# 16Bit_Group_Ripple_Adder.net
KiCad netlist of a schematic drawn in Altium Designer
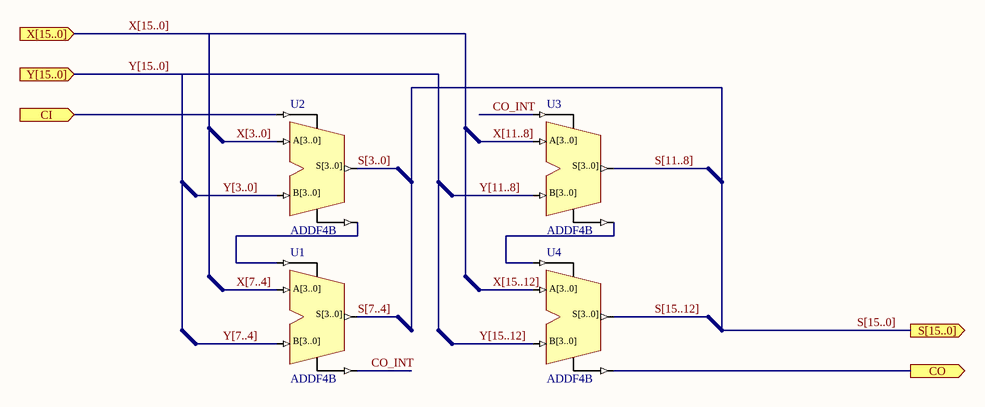
[diagram p0: 16Bit Group Ripple Adder.SchDoc]

(export (version "E")
  (design (tool "Eeschema 10.0.6"))
  (components
    (comp (ref "U1")
      (value "ADDF4B")
      (description "4-Bit Cascadable Unsigned Binary Full Adder, Bus Version")
      (fields (field (name "PUBLISHER") "Altium Limited"))
      (libsource (lib "FPGA Generic") (part "ADDF4B"))
    )
    (comp (ref "U2")
      (value "ADDF4B")
      (description "4-Bit Cascadable Unsigned Binary Full Adder, Bus Version")
      (fields (field (name "PUBLISHER") "Altium Limited"))
      (libsource (lib "FPGA Generic") (part "ADDF4B"))
    )
    (comp (ref "U3")
      (value "ADDF4B")
      (description "4-Bit Cascadable Unsigned Binary Full Adder, Bus Version")
      (fields (field (name "PUBLISHER") "Altium Limited"))
      (libsource (lib "FPGA Generic") (part "ADDF4B"))
    )
    (comp (ref "U4")
      (value "ADDF4B")
      (description "4-Bit Cascadable Unsigned Binary Full Adder, Bus Version")
      (fields (field (name "PUBLISHER") "Altium Limited"))
      (libsource (lib "FPGA Generic") (part "ADDF4B"))
    )
  )
  (nets
    (net (code "49") (name "/CI") (class "Default")
      (node (ref "U2") (pin "CI") (pinfunction "CI_CI") (pintype "input"))
    )
    (net (code "50") (name "/CO") (class "Default")
      (node (ref "U4") (pin "CO") (pinfunction "CO_CO") (pintype "output"))
    )
    (net (code "51") (name "/CO_INT") (class "Default")
      (node (ref "U1") (pin "CO") (pinfunction "CO_CO") (pintype "output"))
      (node (ref "U3") (pin "CI") (pinfunction "CI_CI") (pintype "input"))
    )
    (net (code "52") (name "/S[3..0]") (class "Default")
      (node (ref "U2") (pin "S[3..0]") (pinfunction "S[3..0]_S[3..0]") (pintype "output"))
    )
    (net (code "53") (name "/S[7..4]") (class "Default")
      (node (ref "U1") (pin "S[3..0]") (pinfunction "S[3..0]_S[3..0]") (pintype "output"))
    )
    (net (code "54") (name "/S[11..8]") (class "Default")
      (node (ref "U3") (pin "S[3..0]") (pinfunction "S[3..0]_S[3..0]") (pintype "output"))
    )
    (net (code "56") (name "/S[15..12]") (class "Default")
      (node (ref "U4") (pin "S[3..0]") (pinfunction "S[3..0]_S[3..0]") (pintype "output"))
    )
    (net (code "57") (name "/X[3..0]") (class "Default")
      (node (ref "U2") (pin "A[3..0]") (pinfunction "A[3..0]_A[3..0]") (pintype "input"))
    )
    (net (code "58") (name "/X[7..4]") (class "Default")
      (node (ref "U1") (pin "A[3..0]") (pinfunction "A[3..0]_A[3..0]") (pintype "input"))
    )
    (net (code "59") (name "/X[11..8]") (class "Default")
      (node (ref "U3") (pin "A[3..0]") (pinfunction "A[3..0]_A[3..0]") (pintype "input"))
    )
    (net (code "61") (name "/X[15..12]") (class "Default")
      (node (ref "U4") (pin "A[3..0]") (pinfunction "A[3..0]_A[3..0]") (pintype "input"))
    )
    (net (code "62") (name "/Y[3..0]") (class "Default")
      (node (ref "U2") (pin "B[3..0]") (pinfunction "B[3..0]_B[3..0]") (pintype "input"))
    )
    (net (code "63") (name "/Y[7..4]") (class "Default")
      (node (ref "U1") (pin "B[3..0]") (pinfunction "B[3..0]_B[3..0]") (pintype "input"))
    )
    (net (code "64") (name "/Y[11..8]") (class "Default")
      (node (ref "U3") (pin "B[3..0]") (pinfunction "B[3..0]_B[3..0]") (pintype "input"))
    )
    (net (code "66") (name "/Y[15..12]") (class "Default")
      (node (ref "U4") (pin "B[3..0]") (pinfunction "B[3..0]_B[3..0]") (pintype "input"))
    )
    (net (code "67") (name "Net-(U1-PadCI)") (class "Default")
      (node (ref "U1") (pin "CI") (pinfunction "CI_CI") (pintype "input"))
      (node (ref "U2") (pin "CO") (pinfunction "CO_CO") (pintype "output"))
    )
    (net (code "68") (name "Net-(U3-PadCO)") (class "Default")
      (node (ref "U3") (pin "CO") (pinfunction "CO_CO") (pintype "output"))
      (node (ref "U4") (pin "CI") (pinfunction "CI_CI") (pintype "input"))
    )
  )
)
